# geniecom_sch.net
KiCad netlist of a schematic drawn in EasyEDA
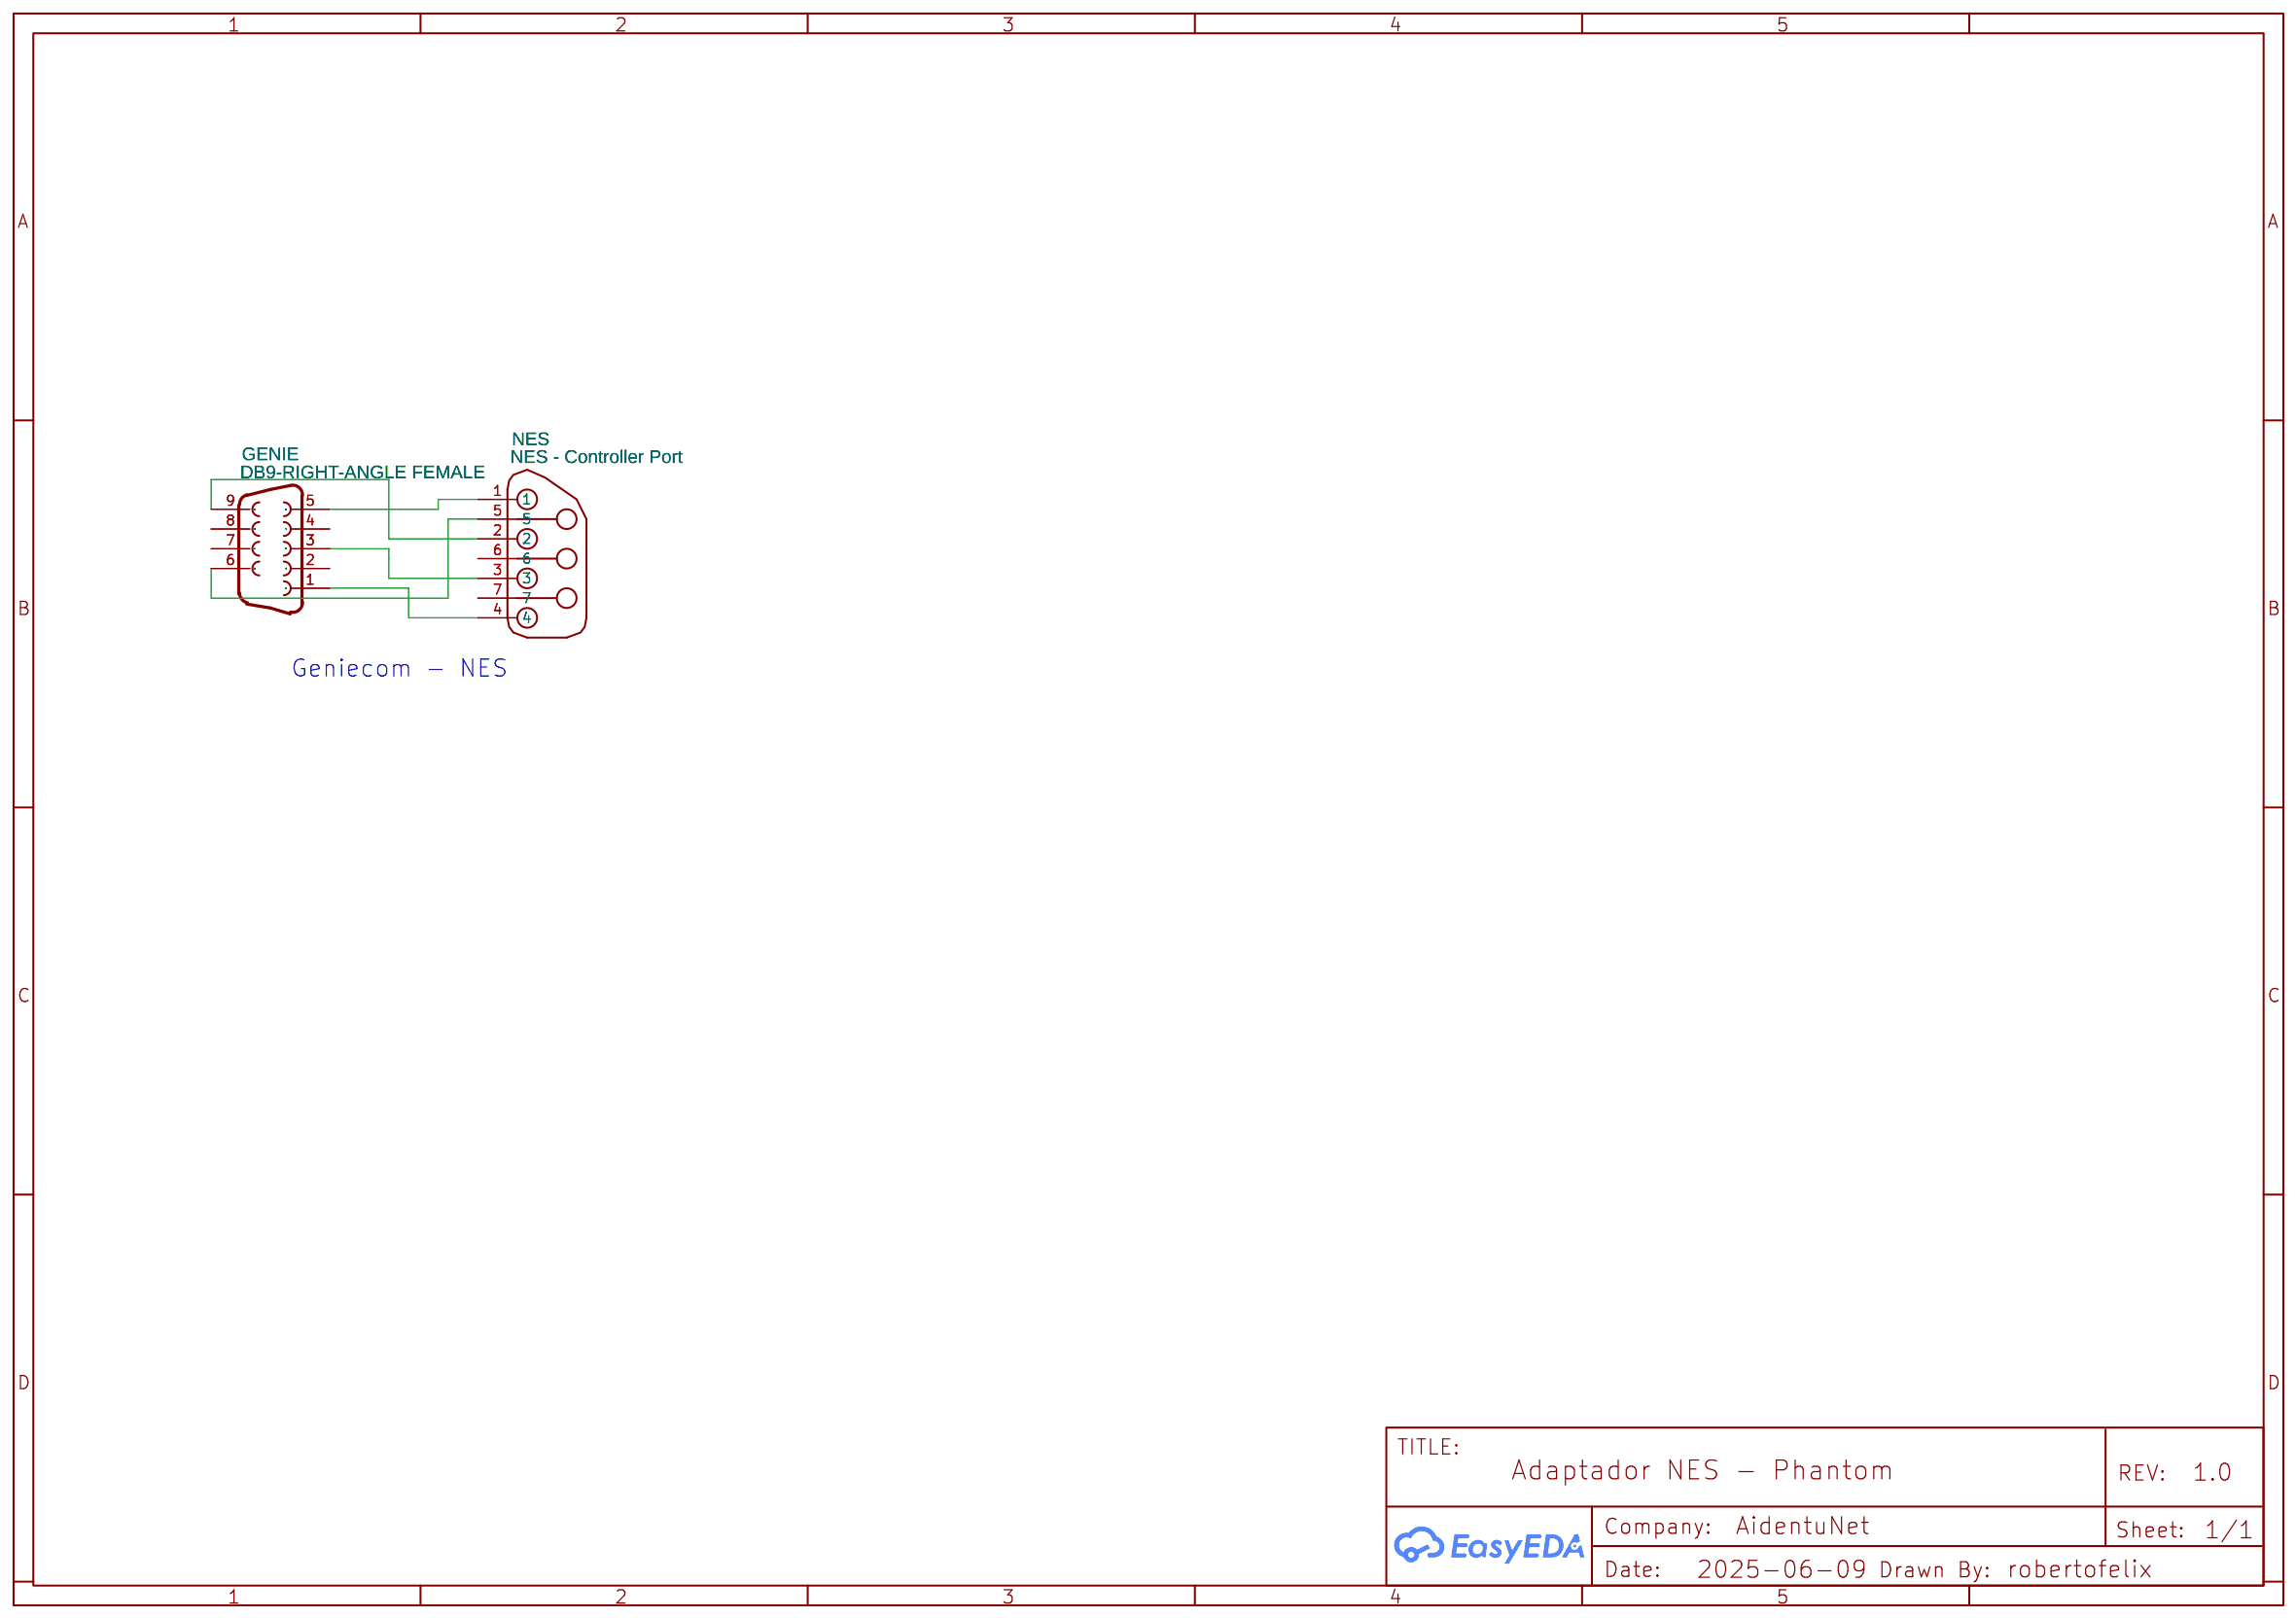
[diagram p0: schematic sheet]

(export (version "E")
  (design (tool "Eeschema 10.0.6"))
  (components
    (comp (ref "GENIE") (value "DB9-RIGHT-ANGLE FEMALE") (libsource (lib "") (part "DB9-RIGHT-ANGLE FEMALE")))
    (comp (ref "NES") (value "NES - Controller Port") (libsource (lib "") (part "NES - Controller Port")))
  )
  (nets
    (net (code "1") (name "Net-(GENIE-Pad1)") (class "Default")
      (node (ref "GENIE") (pin "1") (pinfunction "1_1") (pintype "bidirectional"))
      (node (ref "NES") (pin "4") (pinfunction "4_4") (pintype "unspecified"))
    )
    (net (code "2") (name "Net-(GENIE-Pad3)") (class "Default")
      (node (ref "GENIE") (pin "3") (pinfunction "3_3") (pintype "bidirectional"))
      (node (ref "NES") (pin "3") (pinfunction "3_3") (pintype "unspecified"))
    )
    (net (code "3") (name "Net-(GENIE-Pad5)") (class "Default")
      (node (ref "GENIE") (pin "5") (pinfunction "5_5") (pintype "bidirectional"))
      (node (ref "NES") (pin "1") (pinfunction "1_1") (pintype "unspecified"))
    )
    (net (code "4") (name "Net-(GENIE-Pad6)") (class "Default")
      (node (ref "GENIE") (pin "6") (pinfunction "6_6") (pintype "bidirectional"))
      (node (ref "NES") (pin "5") (pinfunction "5_5") (pintype "unspecified"))
    )
    (net (code "5") (name "Net-(GENIE-Pad9)") (class "Default")
      (node (ref "GENIE") (pin "9") (pinfunction "9_9") (pintype "bidirectional"))
      (node (ref "NES") (pin "2") (pinfunction "2_2") (pintype "unspecified"))
    )
    (net (code "6") (name "unconnected-(GENIE-Pad2)") (class "Default")
      (node (ref "GENIE") (pin "2") (pinfunction "2_2") (pintype "bidirectional"))
    )
    (net (code "7") (name "unconnected-(GENIE-Pad4)") (class "Default")
      (node (ref "GENIE") (pin "4") (pinfunction "4_4") (pintype "bidirectional"))
    )
    (net (code "8") (name "unconnected-(GENIE-Pad7)") (class "Default")
      (node (ref "GENIE") (pin "7") (pinfunction "7_7") (pintype "bidirectional"))
    )
    (net (code "9") (name "unconnected-(GENIE-Pad8)") (class "Default")
      (node (ref "GENIE") (pin "8") (pinfunction "8_8") (pintype "bidirectional"))
    )
    (net (code "10") (name "unconnected-(NES-Pad6)") (class "Default")
      (node (ref "NES") (pin "6") (pinfunction "6_6") (pintype "unspecified"))
    )
    (net (code "11") (name "unconnected-(NES-Pad7)") (class "Default")
      (node (ref "NES") (pin "7") (pinfunction "7_7") (pintype "unspecified"))
    )
  )
)
